# schematic-easyeda.net
KiCad netlist of a schematic drawn in EasyEDA
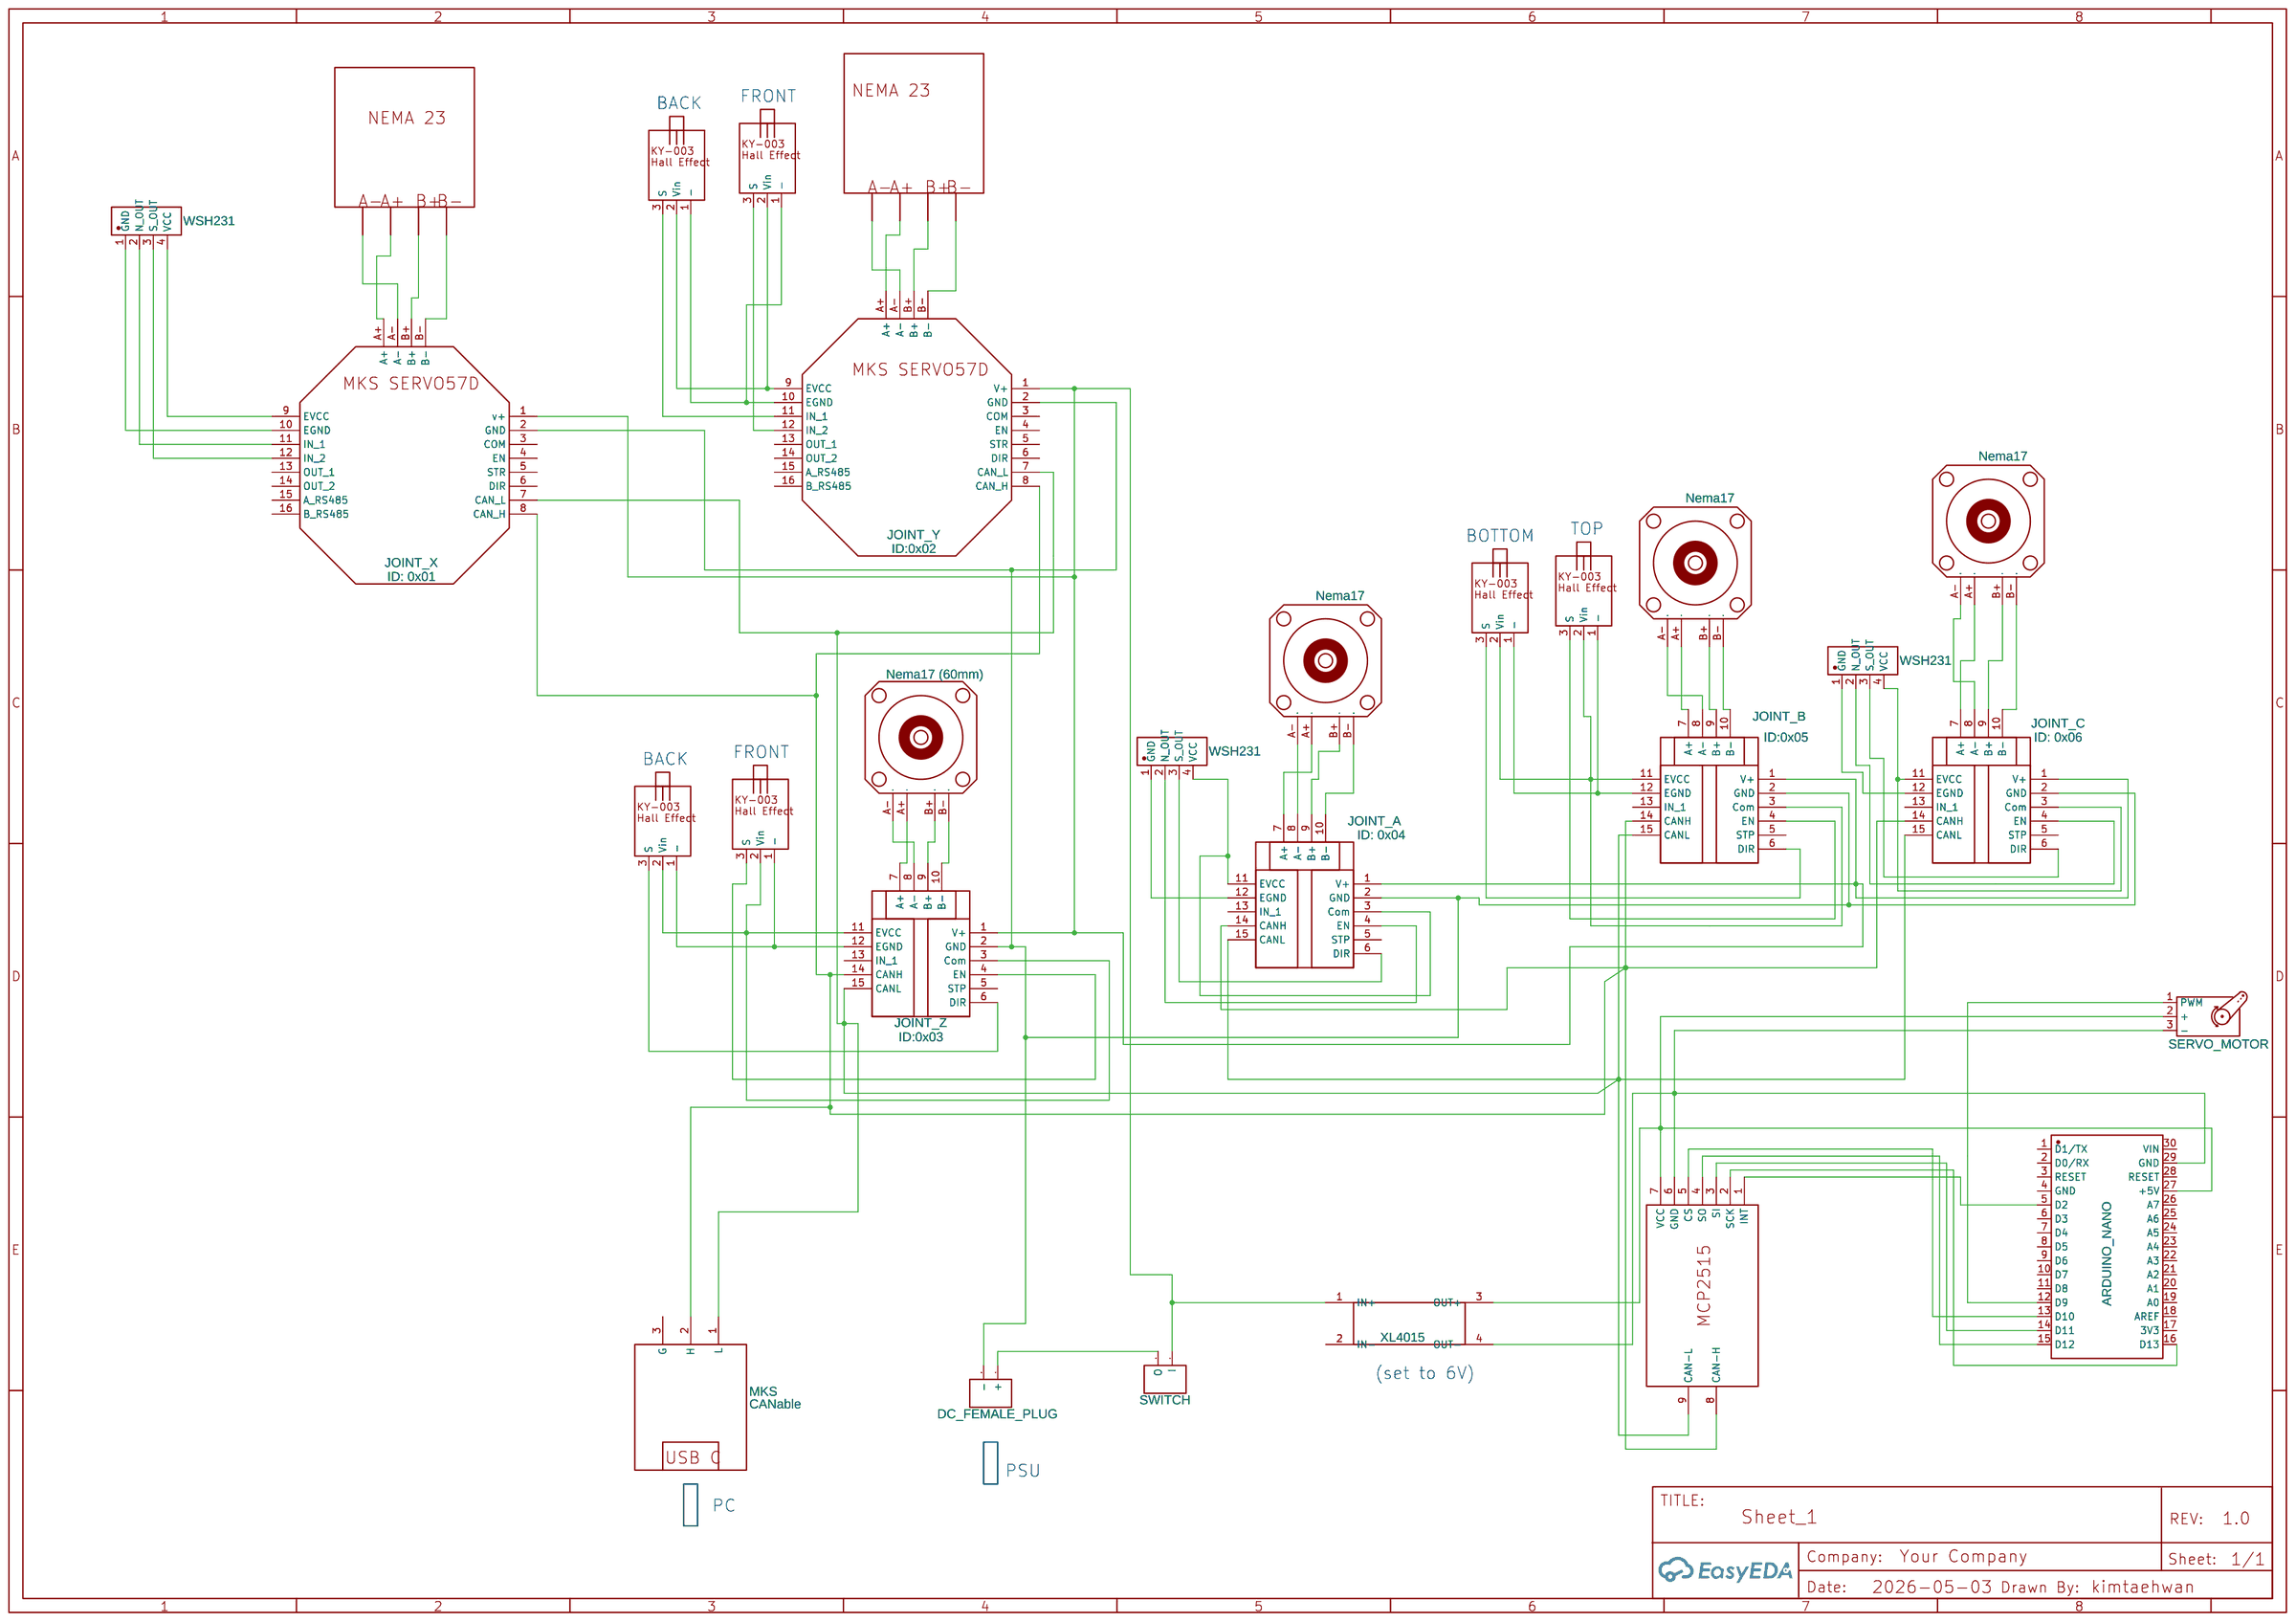
[diagram p0: schematic sheet]

(export (version "E")
  (design (tool "Eeschema 10.0.6"))
  (components
    (comp (ref "CN1")
      (value "WSH231")
      (fields (field (name "Manufacturer Part") "Straight 4 pins magnetic connector Male"))
      (libsource (lib "") (part "STRAIGHT 4 PINS MAGNETIC CONNECTOR MALE"))
    )
    (comp (ref "CN2")
      (value "WSH231")
      (fields (field (name "Manufacturer Part") "Straight 4 pins magnetic connector Male"))
      (libsource (lib "") (part "STRAIGHT 4 PINS MAGNETIC CONNECTOR MALE"))
    )
    (comp (ref "CN3")
      (value "WSH231")
      (fields (field (name "Manufacturer Part") "Straight 4 pins magnetic connector Male"))
      (libsource (lib "") (part "STRAIGHT 4 PINS MAGNETIC CONNECTOR MALE"))
    )
    (comp (ref "H1") (value "SWITCH") (libsource (lib "") (part "HDR-F-2.54_1x2")))
    (comp (ref "H2") (value "DC_FEMALE_PLUG") (libsource (lib "") (part "HDR-F-2.54_1x2_1")))
    (comp (ref "JOINT_A") (value "ID: 0x04") (libsource (lib "") (part "MKS_SERVO42D")))
    (comp (ref "JOINT_B") (value "ID:0x05") (libsource (lib "") (part "MKS_SERVO42D_1")))
    (comp (ref "JOINT_C") (value "ID: 0x06") (libsource (lib "") (part "MKS_SERVO42D_3")))
    (comp (ref "JOINT_X")
      (value "ID: 0x01")
      (fields
        (field (name "Manufacturer Part") "SERVO57D RS485 MB PCBA NEMA23")
        (field (name "Manufacturer") "Makerbase")
      )
      (libsource (lib "") (part "MKS SERVO57D RS485 MB PCBA NEMA23"))
    )
    (comp (ref "JOINT_Y")
      (value "ID:0x02")
      (fields
        (field (name "Manufacturer Part") "SERVO57D RS485 MB PCBA NEMA23")
        (field (name "Manufacturer") "Makerbase")
      )
      (libsource (lib "") (part "MKS SERVO57D RS485 MB PCBA NEMA23_1"))
    )
    (comp (ref "JOINT_Z") (value "ID:0x03") (libsource (lib "") (part "MKS_SERVO42D_2")))
    (comp (ref "M1") (value "SERVO_MOTOR") (libsource (lib "") (part "Motor_Servo")))
    (comp (ref "MKS") (value "CANable") (libsource (lib "") (part "CANable")))
    (comp (ref "MY") (value "Nema17") (libsource (lib "") (part "Nema17")))
    (comp (ref "MY1") (value "Nema17") (libsource (lib "") (part "Nema17")))
    (comp (ref "MY2") (value "Nema17") (libsource (lib "") (part "Nema17")))
    (comp (ref "MY3") (value "Nema17 (60mm)") (libsource (lib "") (part "Nema17")))
    (comp (ref "U1") (value "ARDUINO_NANO") (libsource (lib "") (part "ARDUINO_NANO")))
    (comp (ref "U2") (value "MCP2515CANSPI") (libsource (lib "") (part "MCP2515CANSPI")))
    (comp (ref "U3") (value "XL4015") (libsource (lib "") (part "XL4015DC-DC_symbol")))
    (comp (ref "U4")
      (value "KY-003 Hall Effect Sensor")
      (libsource (lib "") (part "KY-003 Hall Effect Sensor"))
    )
    (comp (ref "U5")
      (value "KY-003 Hall Effect Sensor")
      (libsource (lib "") (part "KY-003 Hall Effect Sensor"))
    )
    (comp (ref "U6")
      (value "KY-003 Hall Effect Sensor")
      (libsource (lib "") (part "KY-003 Hall Effect Sensor"))
    )
    (comp (ref "U7")
      (value "KY-003 Hall Effect Sensor")
      (libsource (lib "") (part "KY-003 Hall Effect Sensor"))
    )
    (comp (ref "U8")
      (value "Nema23")
      (fields (field (name "Manufacturer Part") "57STH56-4004A"))
      (libsource (lib "") (part "Nema23"))
    )
    (comp (ref "U10")
      (value "KY-003 Hall Effect Sensor")
      (libsource (lib "") (part "KY-003 Hall Effect Sensor"))
    )
    (comp (ref "U11")
      (value "KY-003 Hall Effect Sensor")
      (libsource (lib "") (part "KY-003 Hall Effect Sensor"))
    )
    (comp (ref "U12")
      (value "Nema23")
      (fields (field (name "Manufacturer Part") "57STH56-4004A"))
      (libsource (lib "") (part "Nema23_1"))
    )
  )
  (nets
    (net (code "1") (name "Net-(CN1-GND)") (class "Default")
      (node (ref "CN1") (pin "1") (pinfunction "GND_1") (pintype "unspecified"))
      (node (ref "JOINT_C") (pin "12") (pinfunction "EGND_12") (pintype "unspecified"))
    )
    (net (code "2") (name "Net-(CN1-N_OUT)") (class "Default")
      (node (ref "CN1") (pin "2") (pinfunction "N_OUT_2") (pintype "unspecified"))
      (node (ref "JOINT_C") (pin "4") (pinfunction "EN_4") (pintype "unspecified"))
    )
    (net (code "3") (name "Net-(CN1-S_OUT)") (class "Default")
      (node (ref "CN1") (pin "3") (pinfunction "S_OUT_3") (pintype "unspecified"))
      (node (ref "JOINT_C") (pin "6") (pinfunction "DIR_6") (pintype "unspecified"))
    )
    (net (code "4") (name "Net-(CN1-VCC)") (class "Default")
      (node (ref "CN1") (pin "4") (pinfunction "VCC_4") (pintype "unspecified"))
      (node (ref "JOINT_C") (pin "11") (pinfunction "EVCC_11") (pintype "unspecified"))
      (node (ref "JOINT_C") (pin "3") (pinfunction "Com_3") (pintype "unspecified"))
    )
    (net (code "5") (name "Net-(CN2-GND)") (class "Default")
      (node (ref "CN2") (pin "1") (pinfunction "GND_1") (pintype "unspecified"))
      (node (ref "JOINT_A") (pin "12") (pinfunction "EGND_12") (pintype "unspecified"))
    )
    (net (code "6") (name "Net-(CN2-N_OUT)") (class "Default")
      (node (ref "CN2") (pin "2") (pinfunction "N_OUT_2") (pintype "unspecified"))
      (node (ref "JOINT_A") (pin "4") (pinfunction "EN_4") (pintype "unspecified"))
    )
    (net (code "7") (name "Net-(CN2-S_OUT)") (class "Default")
      (node (ref "CN2") (pin "3") (pinfunction "S_OUT_3") (pintype "unspecified"))
      (node (ref "JOINT_A") (pin "6") (pinfunction "DIR_6") (pintype "unspecified"))
    )
    (net (code "8") (name "Net-(CN2-VCC)") (class "Default")
      (node (ref "CN2") (pin "4") (pinfunction "VCC_4") (pintype "unspecified"))
      (node (ref "JOINT_A") (pin "11") (pinfunction "EVCC_11") (pintype "unspecified"))
      (node (ref "JOINT_A") (pin "3") (pinfunction "Com_3") (pintype "unspecified"))
    )
    (net (code "9") (name "Net-(CN3-GND)") (class "Default")
      (node (ref "CN3") (pin "1") (pinfunction "GND_1") (pintype "unspecified"))
      (node (ref "JOINT_X") (pin "10") (pinfunction "EGND_10") (pintype "unspecified"))
    )
    (net (code "10") (name "Net-(CN3-N_OUT)") (class "Default")
      (node (ref "CN3") (pin "2") (pinfunction "N_OUT_2") (pintype "unspecified"))
      (node (ref "JOINT_X") (pin "11") (pinfunction "IN_1_11") (pintype "unspecified"))
    )
    (net (code "11") (name "Net-(CN3-S_OUT)") (class "Default")
      (node (ref "CN3") (pin "3") (pinfunction "S_OUT_3") (pintype "unspecified"))
      (node (ref "JOINT_X") (pin "12") (pinfunction "IN_2_12") (pintype "unspecified"))
    )
    (net (code "12") (name "Net-(CN3-VCC)") (class "Default")
      (node (ref "CN3") (pin "4") (pinfunction "VCC_4") (pintype "unspecified"))
      (node (ref "JOINT_X") (pin "9") (pinfunction "EVCC_9") (pintype "unspecified"))
    )
    (net (code "13") (name "Net-(H1-I)") (class "Default")
      (node (ref "H1") (pin "1") (pinfunction "I_1") (pintype "input"))
      (node (ref "JOINT_A") (pin "1") (pinfunction "V+_1") (pintype "unspecified"))
      (node (ref "JOINT_B") (pin "1") (pinfunction "V+_1") (pintype "unspecified"))
      (node (ref "JOINT_C") (pin "1") (pinfunction "V+_1") (pintype "unspecified"))
      (node (ref "JOINT_X") (pin "1") (pinfunction "v+_1") (pintype "unspecified"))
      (node (ref "JOINT_Y") (pin "1") (pinfunction "V+_1") (pintype "unspecified"))
      (node (ref "JOINT_Z") (pin "1") (pinfunction "V+_1") (pintype "unspecified"))
      (node (ref "U3") (pin "1") (pinfunction "IN+_1") (pintype "unspecified"))
    )
    (net (code "14") (name "Net-(H1-O)") (class "Default")
      (node (ref "H1") (pin "2") (pinfunction "O_2") (pintype "input"))
      (node (ref "H2") (pin "1") (pinfunction "+_1") (pintype "input"))
    )
    (net (code "15") (name "Net-(H2--)") (class "Default")
      (node (ref "H2") (pin "2") (pinfunction "-_2") (pintype "input"))
      (node (ref "JOINT_A") (pin "2") (pinfunction "GND_2") (pintype "unspecified"))
      (node (ref "JOINT_B") (pin "2") (pinfunction "GND_2") (pintype "unspecified"))
      (node (ref "JOINT_C") (pin "2") (pinfunction "GND_2") (pintype "unspecified"))
      (node (ref "JOINT_X") (pin "2") (pinfunction "GND_2") (pintype "unspecified"))
      (node (ref "JOINT_Y") (pin "2") (pinfunction "GND_2") (pintype "unspecified"))
      (node (ref "JOINT_Z") (pin "2") (pinfunction "GND_2") (pintype "unspecified"))
    )
    (net (code "16") (name "Net-(JOINT_A-A+)") (class "Default")
      (node (ref "JOINT_A") (pin "7") (pinfunction "A+_7") (pintype "unspecified"))
      (node (ref "MY2") (pin "A+") (pinfunction "A_A+") (pintype "unspecified"))
    )
    (net (code "17") (name "Net-(JOINT_A-A-)") (class "Default")
      (node (ref "JOINT_A") (pin "8") (pinfunction "A-_8") (pintype "unspecified"))
      (node (ref "MY2") (pin "A-") (pinfunction "B_A-") (pintype "unspecified"))
    )
    (net (code "18") (name "Net-(JOINT_A-B+)") (class "Default")
      (node (ref "JOINT_A") (pin "9") (pinfunction "B+_9") (pintype "unspecified"))
      (node (ref "MY2") (pin "B+") (pinfunction "A_B+") (pintype "unspecified"))
    )
    (net (code "19") (name "Net-(JOINT_A-B-)") (class "Default")
      (node (ref "JOINT_A") (pin "10") (pinfunction "B-_10") (pintype "unspecified"))
      (node (ref "MY2") (pin "B-") (pinfunction "B_B-") (pintype "unspecified"))
    )
    (net (code "20") (name "Net-(JOINT_A-CANH)") (class "Default")
      (node (ref "JOINT_A") (pin "14") (pinfunction "CANH_14") (pintype "unspecified"))
      (node (ref "JOINT_B") (pin "14") (pinfunction "CANH_14") (pintype "unspecified"))
      (node (ref "JOINT_C") (pin "14") (pinfunction "CANH_14") (pintype "unspecified"))
      (node (ref "JOINT_X") (pin "8") (pinfunction "CAN_H_8") (pintype "unspecified"))
      (node (ref "JOINT_Y") (pin "8") (pinfunction "CAN_H_8") (pintype "unspecified"))
      (node (ref "JOINT_Z") (pin "14") (pinfunction "CANH_14") (pintype "unspecified"))
      (node (ref "MKS") (pin "2") (pinfunction "H_2") (pintype "unspecified"))
      (node (ref "U2") (pin "8") (pinfunction "CAN-H_8") (pintype "unspecified"))
    )
    (net (code "21") (name "Net-(JOINT_A-CANL)") (class "Default")
      (node (ref "JOINT_A") (pin "15") (pinfunction "CANL_15") (pintype "unspecified"))
      (node (ref "JOINT_B") (pin "15") (pinfunction "CANL_15") (pintype "unspecified"))
      (node (ref "JOINT_C") (pin "15") (pinfunction "CANL_15") (pintype "unspecified"))
      (node (ref "JOINT_X") (pin "7") (pinfunction "CAN_L_7") (pintype "unspecified"))
      (node (ref "JOINT_Y") (pin "7") (pinfunction "CAN_L_7") (pintype "unspecified"))
      (node (ref "JOINT_Z") (pin "15") (pinfunction "CANL_15") (pintype "unspecified"))
      (node (ref "MKS") (pin "1") (pinfunction "L_1") (pintype "unspecified"))
      (node (ref "U2") (pin "9") (pinfunction "CAN-L_9") (pintype "unspecified"))
    )
    (net (code "22") (name "Net-(JOINT_B-A+)") (class "Default")
      (node (ref "JOINT_B") (pin "7") (pinfunction "A+_7") (pintype "unspecified"))
      (node (ref "MY1") (pin "A+") (pinfunction "A_A+") (pintype "unspecified"))
    )
    (net (code "23") (name "Net-(JOINT_B-A-)") (class "Default")
      (node (ref "JOINT_B") (pin "8") (pinfunction "A-_8") (pintype "unspecified"))
      (node (ref "MY1") (pin "A-") (pinfunction "B_A-") (pintype "unspecified"))
    )
    (net (code "24") (name "Net-(JOINT_B-B+)") (class "Default")
      (node (ref "JOINT_B") (pin "9") (pinfunction "B+_9") (pintype "unspecified"))
      (node (ref "MY1") (pin "B+") (pinfunction "A_B+") (pintype "unspecified"))
    )
    (net (code "25") (name "Net-(JOINT_B-B-)") (class "Default")
      (node (ref "JOINT_B") (pin "10") (pinfunction "B-_10") (pintype "unspecified"))
      (node (ref "MY1") (pin "B-") (pinfunction "B_B-") (pintype "unspecified"))
    )
    (net (code "26") (name "Net-(JOINT_B-Com)") (class "Default")
      (node (ref "JOINT_B") (pin "11") (pinfunction "EVCC_11") (pintype "unspecified"))
      (node (ref "JOINT_B") (pin "3") (pinfunction "Com_3") (pintype "unspecified"))
      (node (ref "U4") (pin "2") (pinfunction "Vin_2") (pintype "unspecified"))
      (node (ref "U5") (pin "2") (pinfunction "Vin_2") (pintype "unspecified"))
    )
    (net (code "27") (name "Net-(JOINT_B-DIR)") (class "Default")
      (node (ref "JOINT_B") (pin "6") (pinfunction "DIR_6") (pintype "unspecified"))
      (node (ref "U5") (pin "3") (pinfunction "S_3") (pintype "unspecified"))
    )
    (net (code "28") (name "Net-(JOINT_B-EGND)") (class "Default")
      (node (ref "JOINT_B") (pin "12") (pinfunction "EGND_12") (pintype "unspecified"))
      (node (ref "U4") (pin "1") (pinfunction "-_1") (pintype "unspecified"))
      (node (ref "U5") (pin "1") (pinfunction "-_1") (pintype "unspecified"))
    )
    (net (code "29") (name "Net-(JOINT_B-EN)") (class "Default")
      (node (ref "JOINT_B") (pin "4") (pinfunction "EN_4") (pintype "unspecified"))
      (node (ref "U4") (pin "3") (pinfunction "S_3") (pintype "unspecified"))
    )
    (net (code "30") (name "Net-(JOINT_C-A+)") (class "Default")
      (node (ref "JOINT_C") (pin "7") (pinfunction "A+_7") (pintype "unspecified"))
      (node (ref "MY") (pin "A+") (pinfunction "A_A+") (pintype "unspecified"))
    )
    (net (code "31") (name "Net-(JOINT_C-A-)") (class "Default")
      (node (ref "JOINT_C") (pin "8") (pinfunction "A-_8") (pintype "unspecified"))
      (node (ref "MY") (pin "A-") (pinfunction "B_A-") (pintype "unspecified"))
    )
    (net (code "32") (name "Net-(JOINT_C-B+)") (class "Default")
      (node (ref "JOINT_C") (pin "9") (pinfunction "B+_9") (pintype "unspecified"))
      (node (ref "MY") (pin "B+") (pinfunction "A_B+") (pintype "unspecified"))
    )
    (net (code "33") (name "Net-(JOINT_C-B-)") (class "Default")
      (node (ref "JOINT_C") (pin "10") (pinfunction "B-_10") (pintype "unspecified"))
      (node (ref "MY") (pin "B-") (pinfunction "B_B-") (pintype "unspecified"))
    )
    (net (code "34") (name "Net-(JOINT_Y-EGND)") (class "Default")
      (node (ref "JOINT_Y") (pin "10") (pinfunction "EGND_10") (pintype "unspecified"))
      (node (ref "U10") (pin "1") (pinfunction "-_1") (pintype "unspecified"))
      (node (ref "U11") (pin "1") (pinfunction "-_1") (pintype "unspecified"))
    )
    (net (code "35") (name "Net-(JOINT_Y-EVCC)") (class "Default")
      (node (ref "JOINT_Y") (pin "9") (pinfunction "EVCC_9") (pintype "unspecified"))
      (node (ref "U10") (pin "2") (pinfunction "Vin_2") (pintype "unspecified"))
      (node (ref "U11") (pin "2") (pinfunction "Vin_2") (pintype "unspecified"))
    )
    (net (code "36") (name "Net-(JOINT_Y-IN_1)") (class "Default")
      (node (ref "JOINT_Y") (pin "11") (pinfunction "IN_1_11") (pintype "unspecified"))
      (node (ref "U11") (pin "3") (pinfunction "S_3") (pintype "unspecified"))
    )
    (net (code "37") (name "Net-(JOINT_Y-IN_2)") (class "Default")
      (node (ref "JOINT_Y") (pin "12") (pinfunction "IN_2_12") (pintype "unspecified"))
      (node (ref "U10") (pin "3") (pinfunction "S_3") (pintype "unspecified"))
    )
    (net (code "38") (name "Net-(JOINT_Z-A+)") (class "Default")
      (node (ref "JOINT_Z") (pin "7") (pinfunction "A+_7") (pintype "unspecified"))
      (node (ref "MY3") (pin "A+") (pinfunction "A_A+") (pintype "unspecified"))
    )
    (net (code "39") (name "Net-(JOINT_Z-A-)") (class "Default")
      (node (ref "JOINT_Z") (pin "8") (pinfunction "A-_8") (pintype "unspecified"))
      (node (ref "MY3") (pin "A-") (pinfunction "B_A-") (pintype "unspecified"))
    )
    (net (code "40") (name "Net-(JOINT_Z-B+)") (class "Default")
      (node (ref "JOINT_Z") (pin "9") (pinfunction "B+_9") (pintype "unspecified"))
      (node (ref "MY3") (pin "B+") (pinfunction "A_B+") (pintype "unspecified"))
    )
    (net (code "41") (name "Net-(JOINT_Z-B-)") (class "Default")
      (node (ref "JOINT_Z") (pin "10") (pinfunction "B-_10") (pintype "unspecified"))
      (node (ref "MY3") (pin "B-") (pinfunction "B_B-") (pintype "unspecified"))
    )
    (net (code "42") (name "Net-(JOINT_Z-Com)") (class "Default")
      (node (ref "JOINT_Z") (pin "11") (pinfunction "EVCC_11") (pintype "unspecified"))
      (node (ref "JOINT_Z") (pin "3") (pinfunction "Com_3") (pintype "unspecified"))
      (node (ref "U6") (pin "2") (pinfunction "Vin_2") (pintype "unspecified"))
      (node (ref "U7") (pin "2") (pinfunction "Vin_2") (pintype "unspecified"))
    )
    (net (code "43") (name "Net-(JOINT_Z-DIR)") (class "Default")
      (node (ref "JOINT_Z") (pin "6") (pinfunction "DIR_6") (pintype "unspecified"))
      (node (ref "U7") (pin "3") (pinfunction "S_3") (pintype "unspecified"))
    )
    (net (code "44") (name "Net-(JOINT_Z-EGND)") (class "Default")
      (node (ref "JOINT_Z") (pin "12") (pinfunction "EGND_12") (pintype "unspecified"))
      (node (ref "U6") (pin "1") (pinfunction "-_1") (pintype "unspecified"))
      (node (ref "U7") (pin "1") (pinfunction "-_1") (pintype "unspecified"))
    )
    (net (code "45") (name "Net-(JOINT_Z-EN)") (class "Default")
      (node (ref "JOINT_Z") (pin "4") (pinfunction "EN_4") (pintype "unspecified"))
      (node (ref "U6") (pin "3") (pinfunction "S_3") (pintype "unspecified"))
    )
    (net (code "46") (name "Net-(M1-+)") (class "Default")
      (node (ref "M1") (pin "2") (pinfunction "+_2") (pintype "unspecified"))
      (node (ref "U1") (pin "27") (pinfunction "+5V_27") (pintype "unspecified"))
      (node (ref "U2") (pin "7") (pinfunction "VCC_7") (pintype "unspecified"))
      (node (ref "U3") (pin "3") (pinfunction "OUT+_3") (pintype "unspecified"))
    )
    (net (code "47") (name "Net-(M1--)") (class "Default")
      (node (ref "M1") (pin "3") (pinfunction "-_3") (pintype "unspecified"))
      (node (ref "U1") (pin "29") (pinfunction "GND_29") (pintype "unspecified"))
      (node (ref "U2") (pin "6") (pinfunction "GND_6") (pintype "unspecified"))
      (node (ref "U3") (pin "4") (pinfunction "OUT-_4") (pintype "unspecified"))
    )
    (net (code "48") (name "Net-(M1-PWM)") (class "Default")
      (node (ref "M1") (pin "1") (pinfunction "PWM_1") (pintype "unspecified"))
      (node (ref "U1") (pin "12") (pinfunction "D9_12") (pintype "unspecified"))
    )
    (net (code "49") (name "Net-(U1-D2)") (class "Default")
      (node (ref "U1") (pin "5") (pinfunction "D2_5") (pintype "unspecified"))
      (node (ref "U2") (pin "1") (pinfunction "INT_1") (pintype "unspecified"))
    )
    (net (code "50") (name "Net-(U1-D10)") (class "Default")
      (node (ref "U1") (pin "13") (pinfunction "D10_13") (pintype "unspecified"))
      (node (ref "U2") (pin "5") (pinfunction "CS_5") (pintype "unspecified"))
    )
    (net (code "51") (name "Net-(U1-D11)") (class "Default")
      (node (ref "U1") (pin "14") (pinfunction "D11_14") (pintype "unspecified"))
      (node (ref "U2") (pin "3") (pinfunction "SI_3") (pintype "unspecified"))
    )
    (net (code "52") (name "Net-(U1-D12)") (class "Default")
      (node (ref "U1") (pin "15") (pinfunction "D12_15") (pintype "unspecified"))
      (node (ref "U2") (pin "4") (pinfunction "SO_4") (pintype "unspecified"))
    )
    (net (code "53") (name "Net-(U1-D13)") (class "Default")
      (node (ref "U1") (pin "16") (pinfunction "D13_16") (pintype "unspecified"))
      (node (ref "U2") (pin "2") (pinfunction "SCK_2") (pintype "unspecified"))
    )
    (net (code "54") (name "unconnected-(JOINT_A-IN_1-Pad13)") (class "Default")
      (node (ref "JOINT_A") (pin "13") (pinfunction "IN_1_13") (pintype "unspecified"))
    )
    (net (code "55") (name "unconnected-(JOINT_A-STP-Pad5)") (class "Default")
      (node (ref "JOINT_A") (pin "5") (pinfunction "STP_5") (pintype "unspecified"))
    )
    (net (code "56") (name "unconnected-(JOINT_B-IN_1-Pad13)") (class "Default")
      (node (ref "JOINT_B") (pin "13") (pinfunction "IN_1_13") (pintype "unspecified"))
    )
    (net (code "57") (name "unconnected-(JOINT_B-STP-Pad5)") (class "Default")
      (node (ref "JOINT_B") (pin "5") (pinfunction "STP_5") (pintype "unspecified"))
    )
    (net (code "58") (name "unconnected-(JOINT_C-IN_1-Pad13)") (class "Default")
      (node (ref "JOINT_C") (pin "13") (pinfunction "IN_1_13") (pintype "unspecified"))
    )
    (net (code "59") (name "unconnected-(JOINT_C-STP-Pad5)") (class "Default")
      (node (ref "JOINT_C") (pin "5") (pinfunction "STP_5") (pintype "unspecified"))
    )
    (net (code "60") (name "unconnected-(JOINT_X-A_RS485-Pad15)") (class "Default")
      (node (ref "JOINT_X") (pin "15") (pinfunction "A_RS485_15") (pintype "unspecified"))
    )
    (net (code "61") (name "unconnected-(JOINT_X-B_RS485-Pad16)") (class "Default")
      (node (ref "JOINT_X") (pin "16") (pinfunction "B_RS485_16") (pintype "unspecified"))
    )
    (net (code "62") (name "unconnected-(JOINT_X-COM-Pad3)") (class "Default")
      (node (ref "JOINT_X") (pin "3") (pinfunction "COM_3") (pintype "unspecified"))
    )
    (net (code "63") (name "unconnected-(JOINT_X-DIR-Pad6)") (class "Default")
      (node (ref "JOINT_X") (pin "6") (pinfunction "DIR_6") (pintype "unspecified"))
    )
    (net (code "64") (name "unconnected-(JOINT_X-EN-Pad4)") (class "Default")
      (node (ref "JOINT_X") (pin "4") (pinfunction "EN_4") (pintype "unspecified"))
    )
    (net (code "65") (name "unconnected-(JOINT_X-OUT_1-Pad13)") (class "Default")
      (node (ref "JOINT_X") (pin "13") (pinfunction "OUT_1_13") (pintype "unspecified"))
    )
    (net (code "66") (name "unconnected-(JOINT_X-OUT_2-Pad14)") (class "Default")
      (node (ref "JOINT_X") (pin "14") (pinfunction "OUT_2_14") (pintype "unspecified"))
    )
    (net (code "67") (name "unconnected-(JOINT_X-PadA+)") (class "Default")
      (node (ref "JOINT_X") (pin "A+") (pinfunction "A+_A+") (pintype "unspecified"))
    )
    (net (code "68") (name "unconnected-(JOINT_X-PadA-)") (class "Default")
      (node (ref "JOINT_X") (pin "A-") (pinfunction "A-_A-") (pintype "unspecified"))
    )
    (net (code "69") (name "unconnected-(JOINT_X-PadB+)") (class "Default")
      (node (ref "JOINT_X") (pin "B+") (pinfunction "B+_B+") (pintype "unspecified"))
    )
    (net (code "70") (name "unconnected-(JOINT_X-PadB-)") (class "Default")
      (node (ref "JOINT_X") (pin "B-") (pinfunction "B-_B-") (pintype "unspecified"))
    )
    (net (code "71") (name "unconnected-(JOINT_X-STR-Pad5)") (class "Default")
      (node (ref "JOINT_X") (pin "5") (pinfunction "STR_5") (pintype "unspecified"))
    )
    (net (code "72") (name "unconnected-(JOINT_Y-A_RS485-Pad15)") (class "Default")
      (node (ref "JOINT_Y") (pin "15") (pinfunction "A_RS485_15") (pintype "unspecified"))
    )
    (net (code "73") (name "unconnected-(JOINT_Y-B_RS485-Pad16)") (class "Default")
      (node (ref "JOINT_Y") (pin "16") (pinfunction "B_RS485_16") (pintype "unspecified"))
    )
    (net (code "74") (name "unconnected-(JOINT_Y-COM-Pad3)") (class "Default")
      (node (ref "JOINT_Y") (pin "3") (pinfunction "COM_3") (pintype "unspecified"))
    )
    (net (code "75") (name "unconnected-(JOINT_Y-DIR-Pad6)") (class "Default")
      (node (ref "JOINT_Y") (pin "6") (pinfunction "DIR_6") (pintype "unspecified"))
    )
    (net (code "76") (name "unconnected-(JOINT_Y-EN-Pad4)") (class "Default")
      (node (ref "JOINT_Y") (pin "4") (pinfunction "EN_4") (pintype "unspecified"))
    )
    (net (code "77") (name "unconnected-(JOINT_Y-OUT_1-Pad13)") (class "Default")
      (node (ref "JOINT_Y") (pin "13") (pinfunction "OUT_1_13") (pintype "unspecified"))
    )
    (net (code "78") (name "unconnected-(JOINT_Y-OUT_2-Pad14)") (class "Default")
      (node (ref "JOINT_Y") (pin "14") (pinfunction "OUT_2_14") (pintype "unspecified"))
    )
    (net (code "79") (name "unconnected-(JOINT_Y-PadA+)") (class "Default")
      (node (ref "JOINT_Y") (pin "A+") (pinfunction "A+_A+") (pintype "unspecified"))
    )
    (net (code "80") (name "unconnected-(JOINT_Y-PadA-)") (class "Default")
      (node (ref "JOINT_Y") (pin "A-") (pinfunction "A-_A-") (pintype "unspecified"))
    )
    (net (code "81") (name "unconnected-(JOINT_Y-PadB+)") (class "Default")
      (node (ref "JOINT_Y") (pin "B+") (pinfunction "B+_B+") (pintype "unspecified"))
    )
    (net (code "82") (name "unconnected-(JOINT_Y-PadB-)") (class "Default")
      (node (ref "JOINT_Y") (pin "B-") (pinfunction "B-_B-") (pintype "unspecified"))
    )
    (net (code "83") (name "unconnected-(JOINT_Y-STR-Pad5)") (class "Default")
      (node (ref "JOINT_Y") (pin "5") (pinfunction "STR_5") (pintype "unspecified"))
    )
    (net (code "84") (name "unconnected-(JOINT_Z-IN_1-Pad13)") (class "Default")
      (node (ref "JOINT_Z") (pin "13") (pinfunction "IN_1_13") (pintype "unspecified"))
    )
    (net (code "85") (name "unconnected-(JOINT_Z-STP-Pad5)") (class "Default")
      (node (ref "JOINT_Z") (pin "5") (pinfunction "STP_5") (pintype "unspecified"))
    )
    (net (code "86") (name "unconnected-(MKS-G-Pad3)") (class "Default")
      (node (ref "MKS") (pin "3") (pinfunction "G_3") (pintype "unspecified"))
    )
    (net (code "87") (name "unconnected-(U1-3V3-Pad17)") (class "Default")
      (node (ref "U1") (pin "17") (pinfunction "3V3_17") (pintype "unspecified"))
    )
    (net (code "88") (name "unconnected-(U1-A0-Pad19)") (class "Default")
      (node (ref "U1") (pin "19") (pinfunction "A0_19") (pintype "unspecified"))
    )
    (net (code "89") (name "unconnected-(U1-A1-Pad20)") (class "Default")
      (node (ref "U1") (pin "20") (pinfunction "A1_20") (pintype "unspecified"))
    )
    (net (code "90") (name "unconnected-(U1-A2-Pad21)") (class "Default")
      (node (ref "U1") (pin "21") (pinfunction "A2_21") (pintype "unspecified"))
    )
    (net (code "91") (name "unconnected-(U1-A3-Pad22)") (class "Default")
      (node (ref "U1") (pin "22") (pinfunction "A3_22") (pintype "unspecified"))
    )
    (net (code "92") (name "unconnected-(U1-A4-Pad23)") (class "Default")
      (node (ref "U1") (pin "23") (pinfunction "A4_23") (pintype "unspecified"))
    )
    (net (code "93") (name "unconnected-(U1-A5-Pad24)") (class "Default")
      (node (ref "U1") (pin "24") (pinfunction "A5_24") (pintype "unspecified"))
    )
    (net (code "94") (name "unconnected-(U1-A6-Pad25)") (class "Default")
      (node (ref "U1") (pin "25") (pinfunction "A6_25") (pintype "unspecified"))
    )
    (net (code "95") (name "unconnected-(U1-A7-Pad26)") (class "Default")
      (node (ref "U1") (pin "26") (pinfunction "A7_26") (pintype "unspecified"))
    )
    (net (code "96") (name "unconnected-(U1-AREF-Pad18)") (class "Default")
      (node (ref "U1") (pin "18") (pinfunction "AREF_18") (pintype "unspecified"))
    )
    (net (code "97") (name "unconnected-(U1-D0{slash}RX-Pad2)") (class "Default")
      (node (ref "U1") (pin "2") (pinfunction "D0/RX_2") (pintype "unspecified"))
    )
    (net (code "98") (name "unconnected-(U1-D1{slash}TX-Pad1)") (class "Default")
      (node (ref "U1") (pin "1") (pinfunction "D1/TX_1") (pintype "unspecified"))
    )
    (net (code "99") (name "unconnected-(U1-D3-Pad6)") (class "Default")
      (node (ref "U1") (pin "6") (pinfunction "D3_6") (pintype "unspecified"))
    )
    (net (code "100") (name "unconnected-(U1-D4-Pad7)") (class "Default")
      (node (ref "U1") (pin "7") (pinfunction "D4_7") (pintype "unspecified"))
    )
    (net (code "101") (name "unconnected-(U1-D5-Pad8)") (class "Default")
      (node (ref "U1") (pin "8") (pinfunction "D5_8") (pintype "unspecified"))
    )
    (net (code "102") (name "unconnected-(U1-D6-Pad9)") (class "Default")
      (node (ref "U1") (pin "9") (pinfunction "D6_9") (pintype "unspecified"))
    )
    (net (code "103") (name "unconnected-(U1-D7-Pad10)") (class "Default")
      (node (ref "U1") (pin "10") (pinfunction "D7_10") (pintype "unspecified"))
    )
    (net (code "104") (name "unconnected-(U1-D8-Pad11)") (class "Default")
      (node (ref "U1") (pin "11") (pinfunction "D8_11") (pintype "unspecified"))
    )
    (net (code "105") (name "unconnected-(U1-GND-Pad4)") (class "Default")
      (node (ref "U1") (pin "4") (pinfunction "GND_4") (pintype "unspecified"))
    )
    (net (code "106") (name "unconnected-(U1-RESET-Pad3)") (class "Default")
      (node (ref "U1") (pin "3") (pinfunction "RESET_3") (pintype "unspecified"))
    )
    (net (code "107") (name "unconnected-(U1-RESET-Pad28)") (class "Default")
      (node (ref "U1") (pin "28") (pinfunction "RESET_28") (pintype "unspecified"))
    )
    (net (code "108") (name "unconnected-(U1-VIN-Pad30)") (class "Default")
      (node (ref "U1") (pin "30") (pinfunction "VIN_30") (pintype "unspecified"))
    )
    (net (code "109") (name "unconnected-(U3-IN--Pad2)") (class "Default")
      (node (ref "U3") (pin "2") (pinfunction "IN-_2") (pintype "unspecified"))
    )
  )
)
